# Schematic_Light_Project_updated.net
KiCad netlist of a schematic drawn in EAGLE
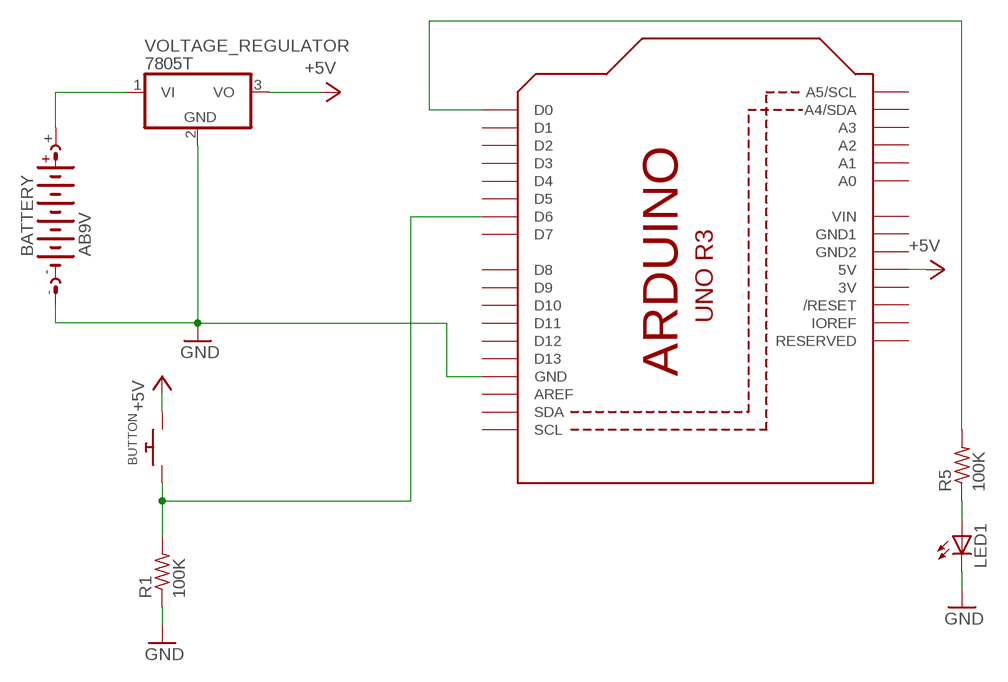
[diagram p0: schematic, sheet 1]

(export (version "E")
  (design (tool "Eeschema 10.0.6"))
  (components
    (comp (ref "ARDUINO")
      (value "ARDUINOR3-DIMENSION")
      (footprint "eagle-import:ARDUINOR3")
      (libsource (lib "eagle-import") (part "ARDUINOR3-DIMENSION"))
    )
    (comp (ref "BATTERY")
      (value "AB9V")
      (footprint "eagle-import:AB9V")
      (libsource (lib "eagle-import") (part "AB9V"))
    )
    (comp (ref "BUTTON")
      (value "SWITCH_PUSHBUTTONSOFTTOUCHSMD_SJ")
      (footprint "eagle-import:PUSHBUTTON_SMD_SJ")
      (libsource (lib "eagle-import") (part "SWITCH_PUSHBUTTONSOFTTOUCHSMD_SJ"))
    )
    (comp (ref "LED1")
      (value "LED5MM")
      (footprint "eagle-import:LED5MM")
      (libsource (lib "eagle-import") (part "LED5MM"))
    )
    (comp (ref "R1")
      (value "100K")
      (footprint "eagle-import:M0805")
      (libsource (lib "eagle-import") (part "R-US_M0805"))
    )
    (comp (ref "R5")
      (value "100K")
      (footprint "eagle-import:M0805")
      (libsource (lib "eagle-import") (part "R-US_M0805"))
    )
    (comp (ref "VOLTAGE_REGULATOR")
      (value "7805T")
      (footprint "eagle-import:TO220H")
      (libsource (lib "eagle-import") (part "78T05"))
    )
  )
  (nets
    (net (code "1") (name "+5V") (class "Default")
      (node (ref "ARDUINO") (pin "5V") (pinfunction "5V_5V") (pintype "power_in"))
      (node (ref "BUTTON") (pin "P$2") (pinfunction "P$2_P$2") (pintype "passive"))
      (node (ref "VOLTAGE_REGULATOR") (pin "3") (pinfunction "VO_3") (pintype "passive"))
    )
    (net (code "2") (name "/3V") (class "Default")
      (node (ref "ARDUINO") (pin "3V") (pinfunction "3V_3V") (pintype "power_in"))
    )
    (net (code "3") (name "/GND1") (class "Default")
      (node (ref "ARDUINO") (pin "GND1") (pinfunction "GND1_GND1") (pintype "power_in"))
    )
    (net (code "4") (name "/GND2") (class "Default")
      (node (ref "ARDUINO") (pin "GND2") (pinfunction "GND2_GND2") (pintype "power_in"))
    )
    (net (code "5") (name "/VIN") (class "Default")
      (node (ref "ARDUINO") (pin "VIN") (pinfunction "VIN_VIN") (pintype "power_in"))
    )
    (net (code "6") (name "GND") (class "Default")
      (node (ref "ARDUINO") (pin "GND") (pinfunction "GND_GND") (pintype "power_in"))
      (node (ref "BATTERY") (pin "-") (pinfunction "-_-") (pintype "passive"))
      (node (ref "LED1") (pin "K") (pinfunction "C_K") (pintype "passive"))
      (node (ref "R1") (pin "1") (pinfunction "1_1") (pintype "passive"))
      (node (ref "VOLTAGE_REGULATOR") (pin "2") (pinfunction "GND_2") (pintype "passive"))
    )
    (net (code "7") (name "Net-(ARDUINO-PadD0)") (class "Default")
      (node (ref "ARDUINO") (pin "D0") (pinfunction "D0_D0") (pintype "bidirectional"))
      (node (ref "R5") (pin "2") (pinfunction "2_2") (pintype "passive"))
    )
    (net (code "8") (name "Net-(ARDUINO-PadD6)") (class "Default")
      (node (ref "ARDUINO") (pin "D6") (pinfunction "D6_D6") (pintype "bidirectional"))
      (node (ref "BUTTON") (pin "P$1") (pinfunction "P$1_P$1") (pintype "passive"))
      (node (ref "R1") (pin "2") (pinfunction "2_2") (pintype "passive"))
    )
    (net (code "9") (name "Net-(LED1-PadA)") (class "Default")
      (node (ref "LED1") (pin "A") (pinfunction "A_A") (pintype "passive"))
      (node (ref "R5") (pin "1") (pinfunction "1_1") (pintype "passive"))
    )
    (net (code "10") (name "Net-(VOLTAGE_REGULATOR-VI)") (class "Default")
      (node (ref "BATTERY") (pin "+") (pinfunction "+_+") (pintype "passive"))
      (node (ref "VOLTAGE_REGULATOR") (pin "1") (pinfunction "VI_1") (pintype "input"))
    )
    (net (code "11") (name "unconnected-(ARDUINO-A4{slash}SDA-PadA4)") (class "Default")
      (node (ref "ARDUINO") (pin "A4") (pinfunction "A4/SDA_A4") (pintype "bidirectional"))
    )
    (net (code "12") (name "unconnected-(ARDUINO-A5{slash}SCL-PadA5)") (class "Default")
      (node (ref "ARDUINO") (pin "A5") (pinfunction "A5/SCL_A5") (pintype "bidirectional"))
    )
    (net (code "13") (name "unconnected-(ARDUINO-PadA0)") (class "Default")
      (node (ref "ARDUINO") (pin "A0") (pinfunction "A0_A0") (pintype "bidirectional"))
    )
    (net (code "14") (name "unconnected-(ARDUINO-PadA1)") (class "Default")
      (node (ref "ARDUINO") (pin "A1") (pinfunction "A1_A1") (pintype "bidirectional"))
    )
    (net (code "15") (name "unconnected-(ARDUINO-PadA2)") (class "Default")
      (node (ref "ARDUINO") (pin "A2") (pinfunction "A2_A2") (pintype "bidirectional"))
    )
    (net (code "16") (name "unconnected-(ARDUINO-PadA3)") (class "Default")
      (node (ref "ARDUINO") (pin "A3") (pinfunction "A3_A3") (pintype "bidirectional"))
    )
    (net (code "17") (name "unconnected-(ARDUINO-PadAREF)") (class "Default")
      (node (ref "ARDUINO") (pin "AREF") (pinfunction "AREF_AREF") (pintype "bidirectional"))
    )
    (net (code "18") (name "unconnected-(ARDUINO-PadD1)") (class "Default")
      (node (ref "ARDUINO") (pin "D1") (pinfunction "D1_D1") (pintype "bidirectional"))
    )
    (net (code "19") (name "unconnected-(ARDUINO-PadD2)") (class "Default")
      (node (ref "ARDUINO") (pin "D2") (pinfunction "D2_D2") (pintype "bidirectional"))
    )
    (net (code "20") (name "unconnected-(ARDUINO-PadD3)") (class "Default")
      (node (ref "ARDUINO") (pin "D3") (pinfunction "D3_D3") (pintype "bidirectional"))
    )
    (net (code "21") (name "unconnected-(ARDUINO-PadD4)") (class "Default")
      (node (ref "ARDUINO") (pin "D4") (pinfunction "D4_D4") (pintype "bidirectional"))
    )
    (net (code "22") (name "unconnected-(ARDUINO-PadD5)") (class "Default")
      (node (ref "ARDUINO") (pin "D5") (pinfunction "D5_D5") (pintype "bidirectional"))
    )
    (net (code "23") (name "unconnected-(ARDUINO-PadD7)") (class "Default")
      (node (ref "ARDUINO") (pin "D7") (pinfunction "D7_D7") (pintype "bidirectional"))
    )
    (net (code "24") (name "unconnected-(ARDUINO-PadD8)") (class "Default")
      (node (ref "ARDUINO") (pin "D8") (pinfunction "D8_D8") (pintype "bidirectional"))
    )
    (net (code "25") (name "unconnected-(ARDUINO-PadD9)") (class "Default")
      (node (ref "ARDUINO") (pin "D9") (pinfunction "D9_D9") (pintype "bidirectional"))
    )
    (net (code "26") (name "unconnected-(ARDUINO-PadD10)") (class "Default")
      (node (ref "ARDUINO") (pin "D10") (pinfunction "D10_D10") (pintype "bidirectional"))
    )
    (net (code "27") (name "unconnected-(ARDUINO-PadD11)") (class "Default")
      (node (ref "ARDUINO") (pin "D11") (pinfunction "D11_D11") (pintype "bidirectional"))
    )
    (net (code "28") (name "unconnected-(ARDUINO-PadD12)") (class "Default")
      (node (ref "ARDUINO") (pin "D12") (pinfunction "D12_D12") (pintype "bidirectional"))
    )
    (net (code "29") (name "unconnected-(ARDUINO-PadD13)") (class "Default")
      (node (ref "ARDUINO") (pin "D13") (pinfunction "D13_D13") (pintype "bidirectional"))
    )
    (net (code "30") (name "unconnected-(ARDUINO-PadIOREF)") (class "Default")
      (node (ref "ARDUINO") (pin "IOREF") (pinfunction "IOREF_IOREF") (pintype "output"))
    )
    (net (code "31") (name "unconnected-(ARDUINO-PadRESERVED)") (class "Default")
      (node (ref "ARDUINO") (pin "RESERVED") (pinfunction "RESERVED_RESERVED") (pintype "no_connect"))
    )
    (net (code "32") (name "unconnected-(ARDUINO-PadSCL)") (class "Default")
      (node (ref "ARDUINO") (pin "SCL") (pinfunction "SCL_SCL") (pintype "bidirectional"))
    )
    (net (code "33") (name "unconnected-(ARDUINO-PadSDA)") (class "Default")
      (node (ref "ARDUINO") (pin "SDA") (pinfunction "SDA_SDA") (pintype "bidirectional"))
    )
    (net (code "34") (name "unconnected-(ARDUINO-{slash}RESET-PadRESET)") (class "Default")
      (node (ref "ARDUINO") (pin "RESET") (pinfunction "/RESET_RESET") (pintype "bidirectional"))
    )
  )
)
